# 28-MIPI_60_PIN_CONNECTOR.net
KiCad netlist of a schematic drawn in Altium Designer
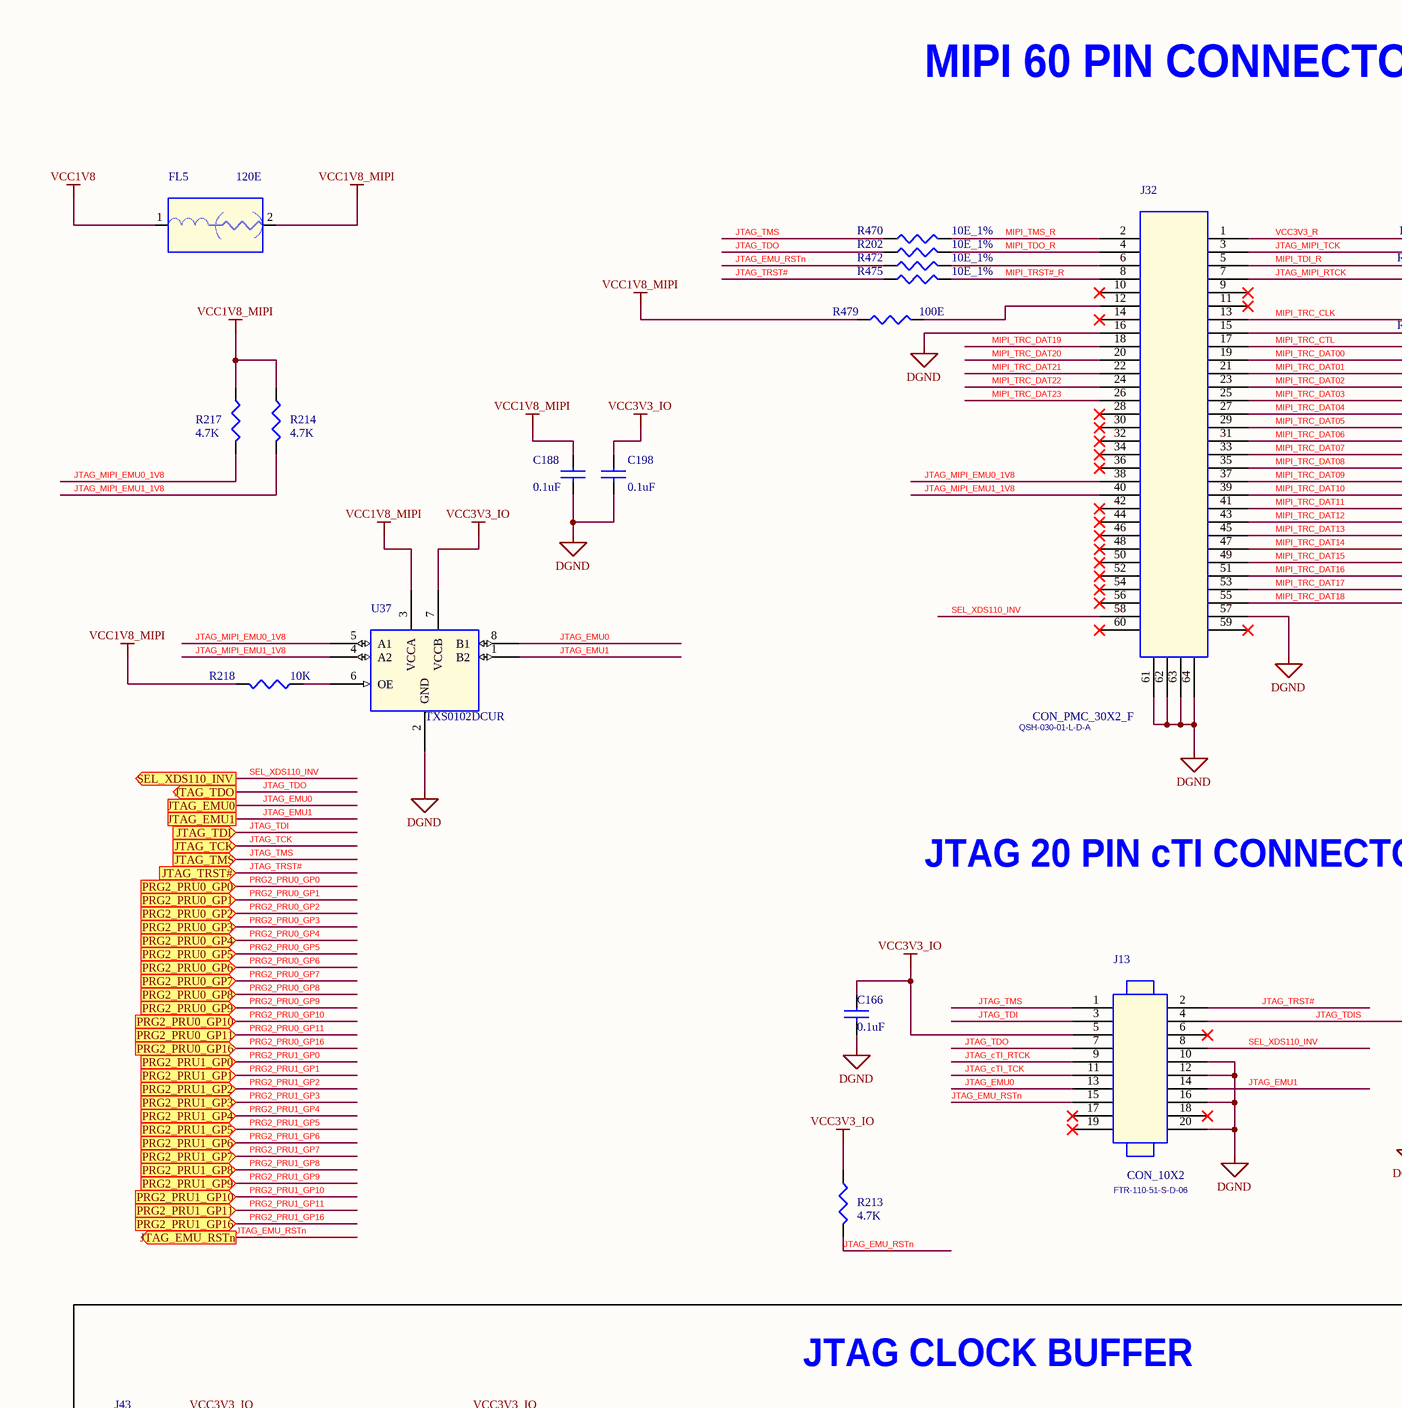
[diagram p0: 28-MIPI 60 PIN CONNECTOR.SchDoc, top left]
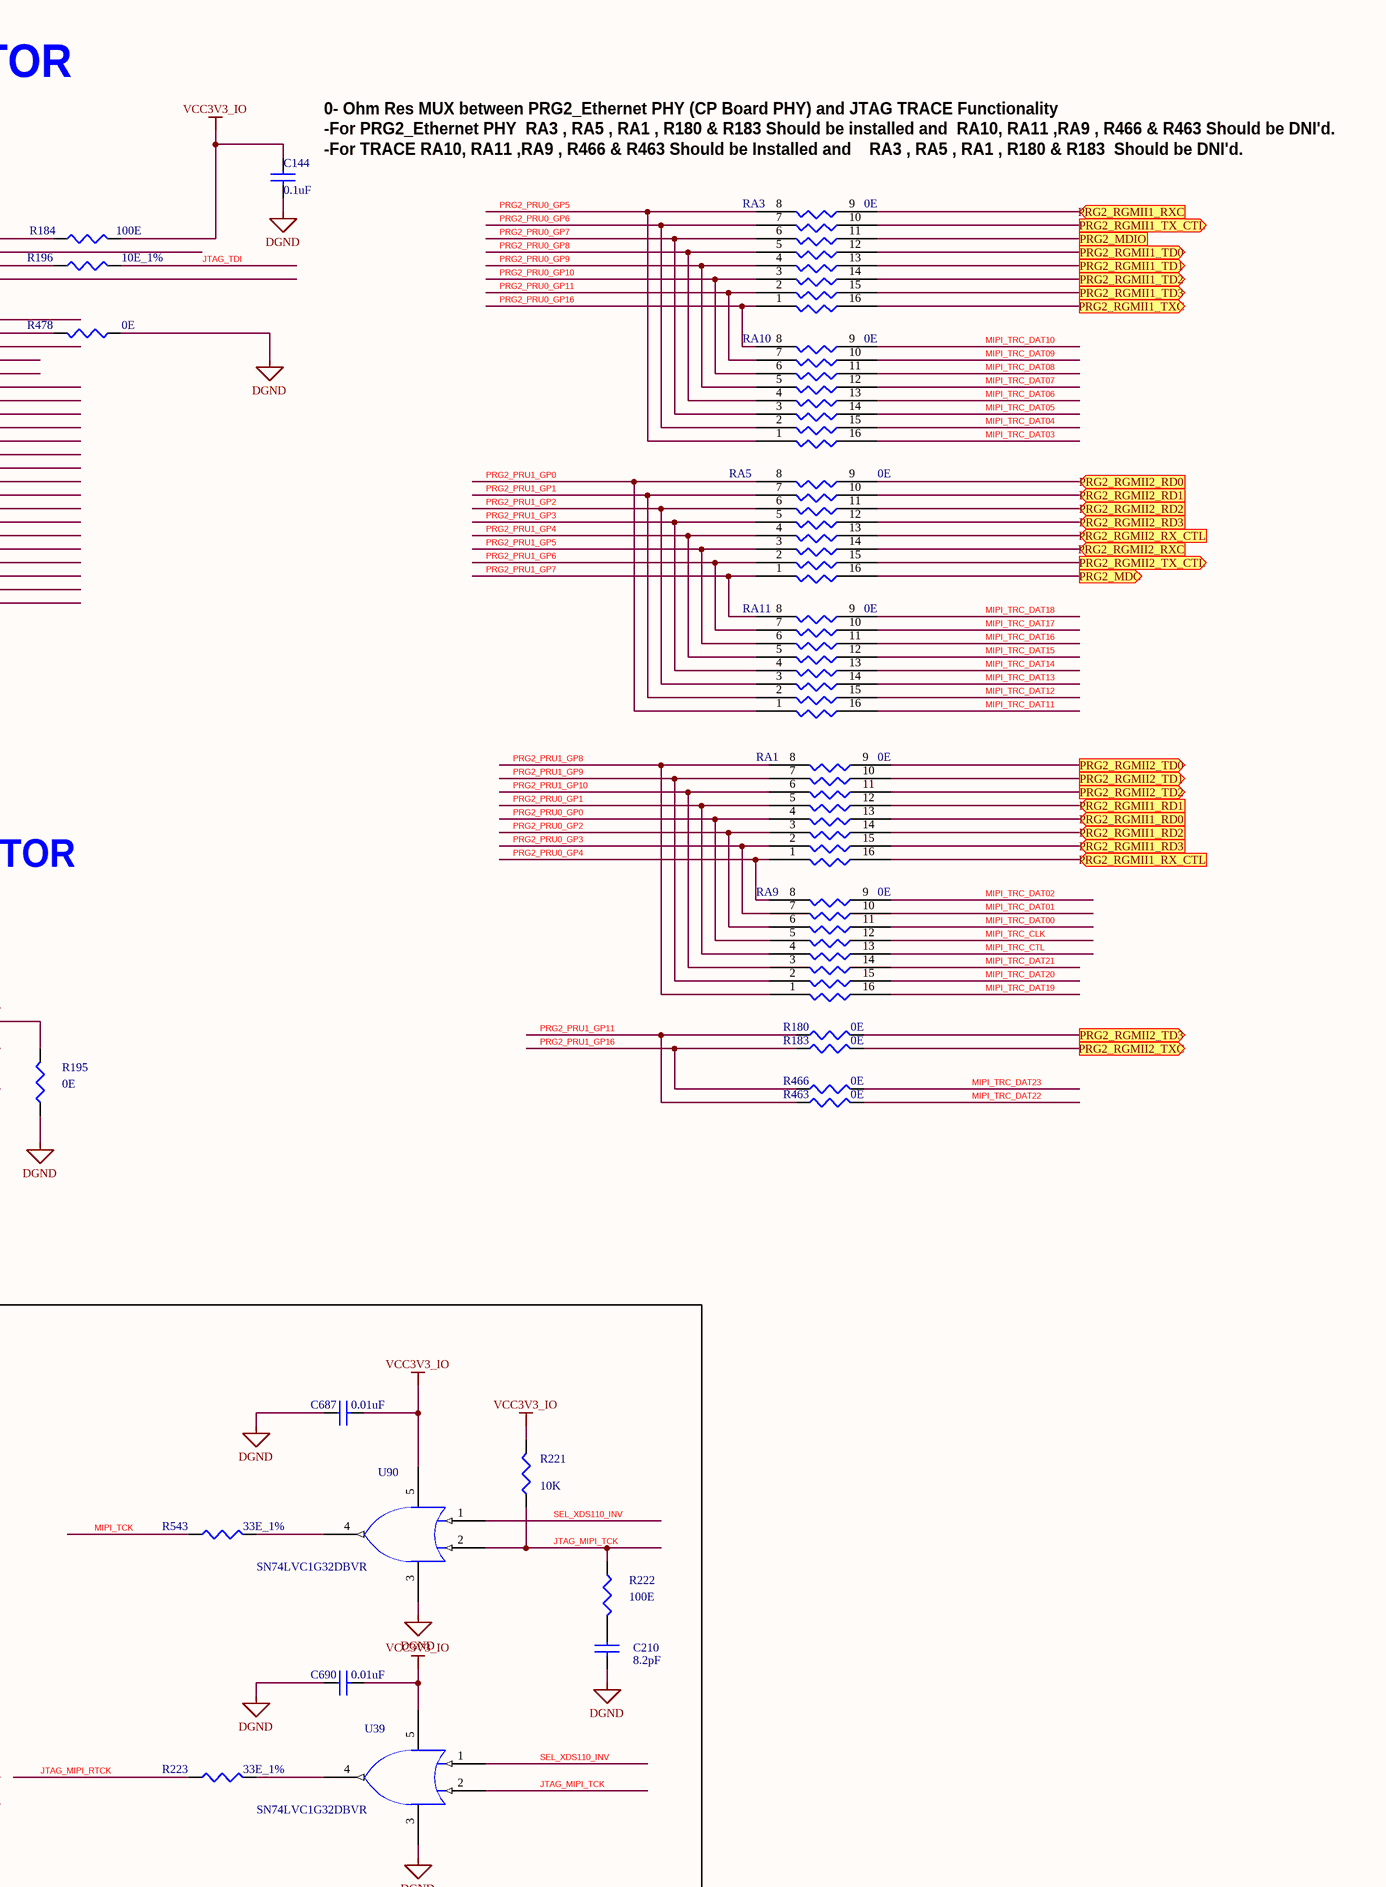
[diagram p1: 28-MIPI 60 PIN CONNECTOR.SchDoc, top right]
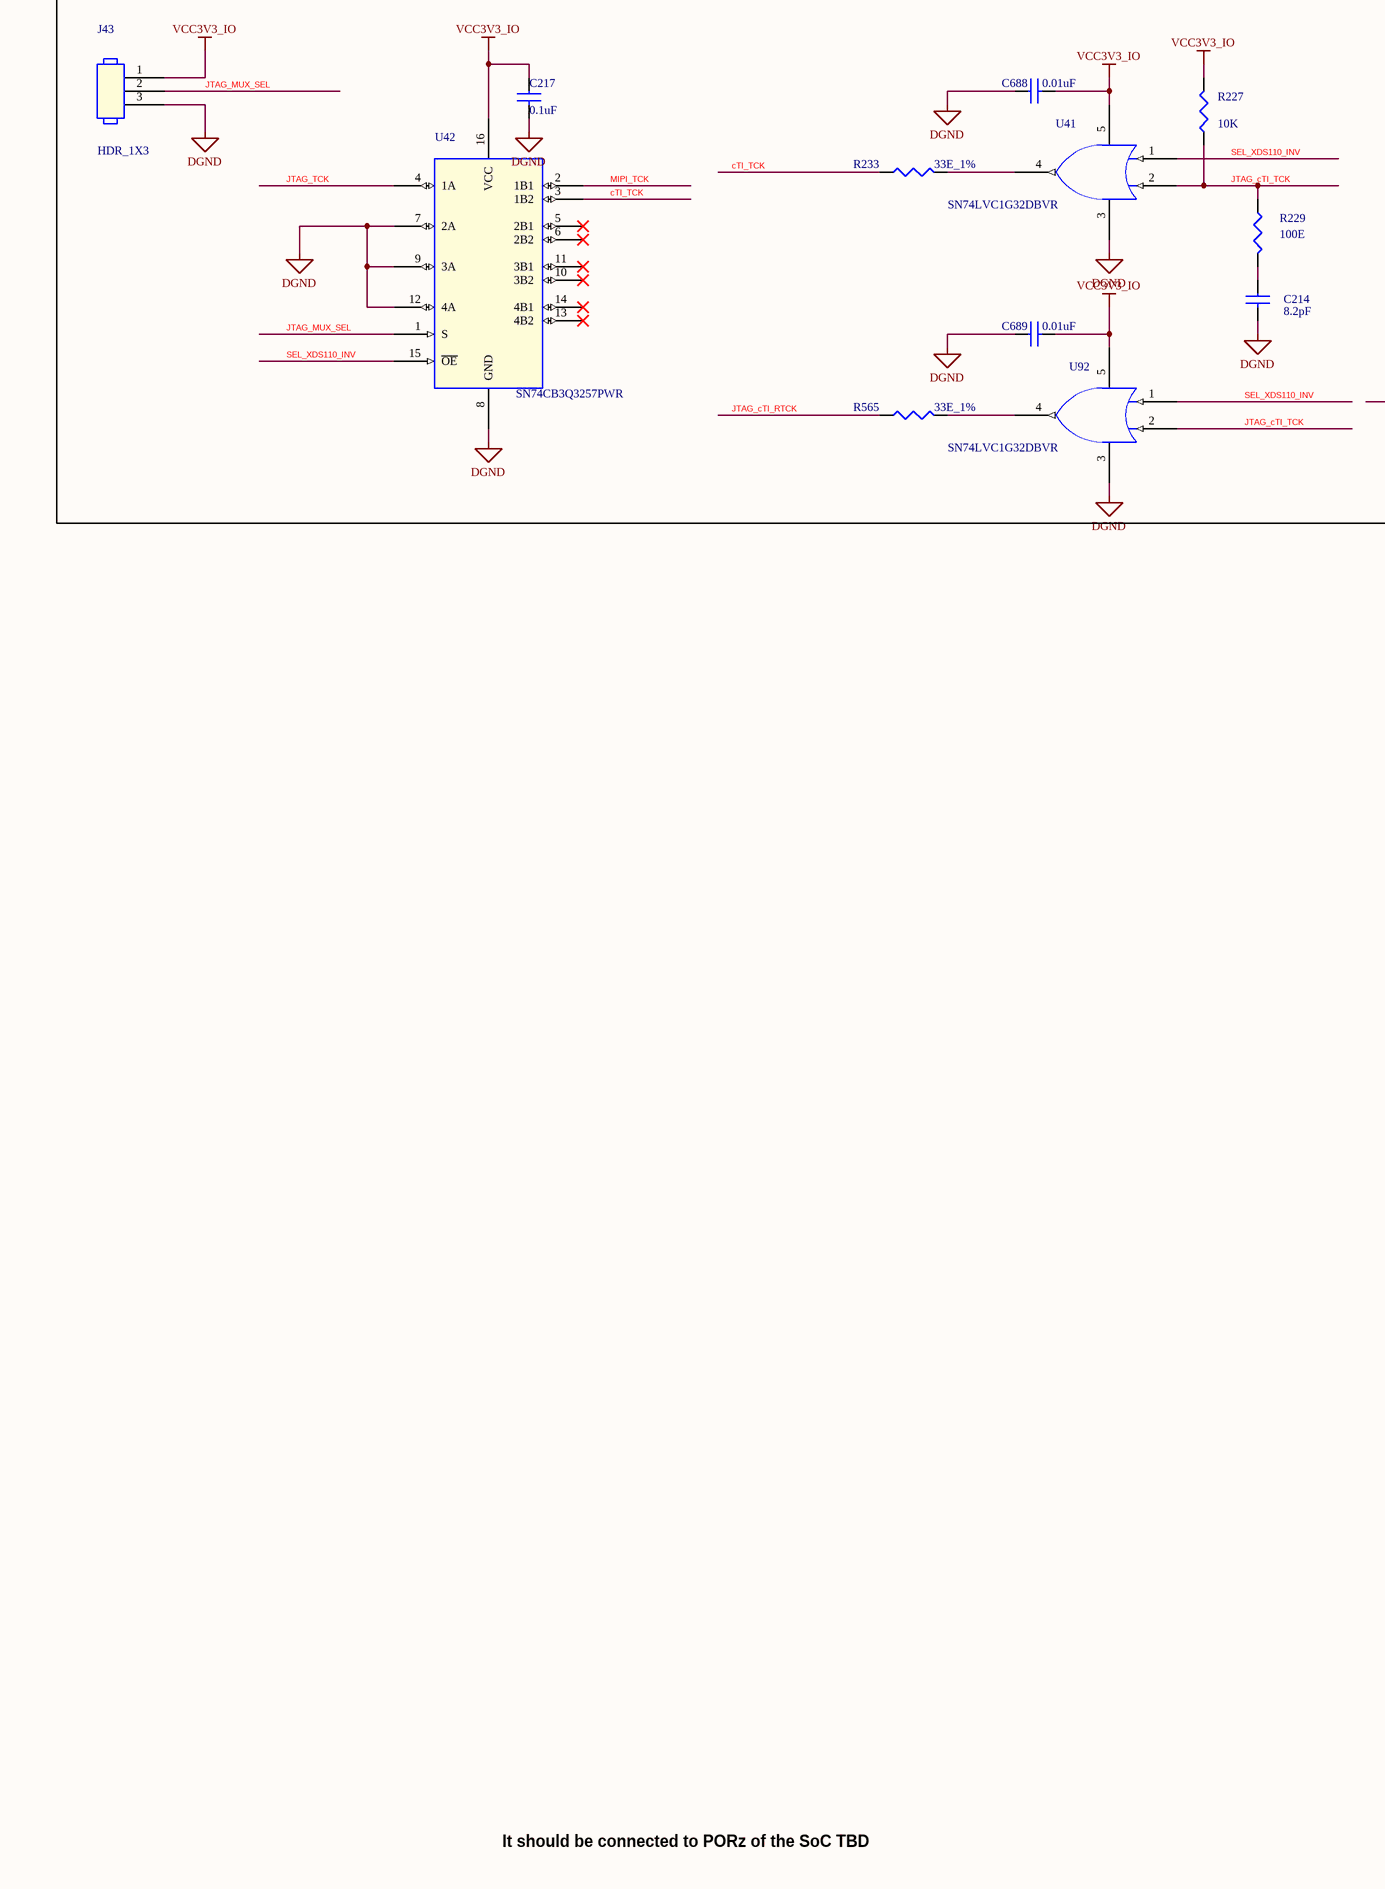
[diagram p2: 28-MIPI 60 PIN CONNECTOR.SchDoc, bottom left]
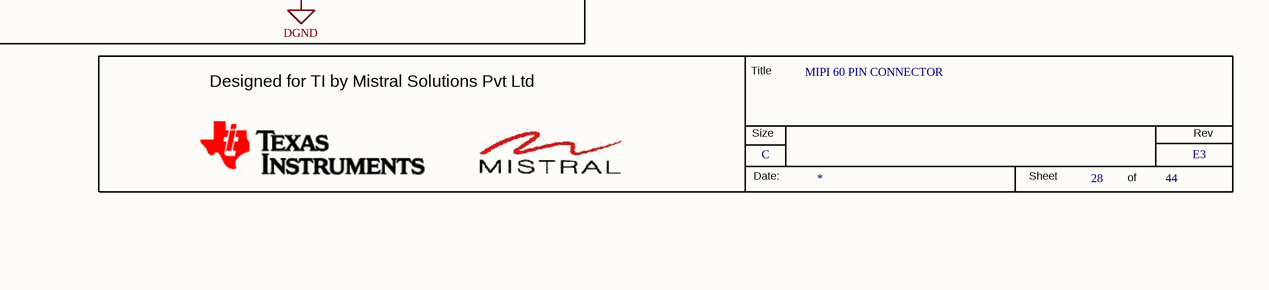
[diagram p3: 28-MIPI 60 PIN CONNECTOR.SchDoc, bottom right]

(export (version "E")
  (design (tool "Eeschema 10.0.6"))
  (components
    (comp (ref "C144")
      (value "0.1uF")
      (footprint "CAP0201_0-5")
      (description "CAP CERAMIC 0.1uF 16V 10% X5R 0201")
      (fields
        (field (name "MISTRAL PART NO") "120009030072-R")
        (field (name "MFR_PART_NUMBER") "GRM033R61C104KE84J")
      )
      (libsource (lib "*") (part "CAP_Dup5"))
    )
    (comp (ref "C166")
      (value "0.1uF")
      (footprint "CAP0201_0-5")
      (description "CAP CERAMIC 0.1uF 16V 10% X5R 0201")
      (fields
        (field (name "MISTRAL PART NO") "120009030072-R")
        (field (name "MFR_PART_NUMBER") "GRM033R61C104KE84J")
      )
      (libsource (lib "*") (part "CAP_Dup5"))
    )
    (comp (ref "C188")
      (value "0.1uF")
      (footprint "CAP0201_0-5")
      (description "CAP CERAMIC 0.1uF 16V 10% X5R 0201")
      (fields (field (name "DISTRIBUTOR_PART_NUMBER") "490-16742-1-ND") (field (name "VOLTAGE") "16V"))
      (libsource (lib "*") (part "CAP_Dup5"))
    )
    (comp (ref "C198")
      (value "0.1uF")
      (footprint "CAP0201_0-5")
      (description "CAP CERAMIC 0.1uF 16V 10% X5R 0201")
      (fields
        (field (name "MISTRAL PART NO") "120009030072-R")
        (field (name "MFR_PART_NUMBER") "GRM033R61C104KE84J")
      )
      (libsource (lib "*") (part "CAP_Dup5"))
    )
    (comp (ref "C210")
      (value "8.2pF")
      (footprint "CAP0402_0-75")
      (description "CAP CERAMIC 8.2pF 50V 0.5pF C0G(NP0) 0402")
      (fields (field (name "DISTRIBUTOR_PART_NUMBER") "GCM1555C1H8R2DA16D-ND") (field (name "VOLTAGE") "50V"))
      (libsource (lib "*") (part "CAP_Dup5"))
    )
    (comp (ref "C214")
      (value "8.2pF")
      (footprint "CAP0402_0-75")
      (description "CAP CERAMIC 8.2pF 50V 0.5pF C0G(NP0) 0402")
      (fields (field (name "DISTRIBUTOR_PART_NUMBER") "GCM1555C1H8R2DA16D-ND") (field (name "VOLTAGE") "50V"))
      (libsource (lib "*") (part "CAP_Dup5"))
    )
    (comp (ref "C217")
      (value "0.1uF")
      (footprint "CAP0201_0-5")
      (description "CAP CERAMIC 0.1uF 16V 10% X5R 0201")
      (fields (field (name "DISTRIBUTOR_PART_NUMBER") "490-16742-1-ND") (field (name "VOLTAGE") "16V"))
      (libsource (lib "*") (part "CAP_Dup4"))
    )
    (comp (ref "C687")
      (value "0.01uF")
      (footprint "CAP0201_0-5")
      (description "CAP CERAMIC 0.01uF 25V 10% X5R 0201")
      (fields (field (name "DISTRIBUTOR_PART_NUMBER") "GRM033R61E103KA12J-ND") (field (name "VOLTAGE") "25V"))
      (libsource (lib "*") (part "CAP_Dup5"))
    )
    (comp (ref "C688")
      (value "0.01uF")
      (footprint "CAP0201_0-5")
      (description "CAP CERAMIC 0.01uF 25V 10% X5R 0201")
      (fields (field (name "DISTRIBUTOR_PART_NUMBER") "GRM033R61E103KA12J-ND") (field (name "VOLTAGE") "25V"))
      (libsource (lib "*") (part "CAP_Dup5"))
    )
    (comp (ref "C689")
      (value "0.01uF")
      (footprint "CAP0201_0-5")
      (description "CAP CERAMIC 0.01uF 25V 10% X5R 0201")
      (fields (field (name "DISTRIBUTOR_PART_NUMBER") "GRM033R61E103KA12J-ND") (field (name "VOLTAGE") "25V"))
      (libsource (lib "*") (part "CAP_Dup5"))
    )
    (comp (ref "C690")
      (value "0.01uF")
      (footprint "CAP0201_0-5")
      (description "CAP CERAMIC 0.01uF 25V 10% X5R 0201")
      (fields (field (name "DISTRIBUTOR_PART_NUMBER") "GRM033R61E103KA12J-ND") (field (name "VOLTAGE") "25V"))
      (libsource (lib "*") (part "CAP_Dup5"))
    )
    (comp (ref "FL5")
      (value "120E")
      (footprint "EMIFIL_BLM15A_0402_0-6")
      (description "FERRITE CHIP 120E 1.3A 0402")
      (fields (field (name "DISTRIBUTOR_PART_NUMBER") "490-5203-1-ND") (field (name "VOLTAGE") "NA"))
      (libsource (lib "*") (part "EMIFILTER_IND"))
    )
    (comp (ref "J13")
      (value "CON_10X2")
      (footprint "CON_10X2_FTR-110-51-S-D_P_S_S")
      (description "CON 10X2 1.27MM PITCH MALE SMD")
      (fields
        (field (name "DISTRIBUTOR_PART_NUMBER") "FTR-110-51-S-D-06-ND")
        (field (name "VOLTAGE") "NA")
        (field (name "MFR_PART_NUMBER") "FTR-110-51-S-D-06")
      )
      (libsource (lib "*") (part "CON_10X2"))
    )
    (comp (ref "J32")
      (value "CON_PMC_30X2_F")
      (footprint "CON_PMC30X2_QSH-030-01-L_S_S_S")
      (description "CON PMC 30X2 0.50MM PITCH FEMALE ST SMD")
      (fields
        (field (name "MISTRAL PART NO") "150009030606")
        (field (name "MFR_PART_NUMBER") "QSH-030-01-L-D-A")
      )
      (libsource (lib "*") (part "CON_PMC_30X2_F"))
    )
    (comp (ref "J43")
      (value "HDR_1X3")
      (footprint "HDR_3X1_100_S_T")
      (description "HDR 1X3 2.54MM PITCH ST TH")
      (fields (field (name "DISTRIBUTOR_PART_NUMBER") "609-3471-ND") (field (name "VOLTAGE") "NA"))
      (libsource (lib "*") (part "HEADER_3X1"))
    )
    (comp (ref "R180")
      (value "0E")
      (footprint "RES0402_0-5")
      (description "RES 0E 1/16W 0402")
      (fields (field (name "DISTRIBUTOR_PART_NUMBER") "541-0.0JCT-ND") (field (name "VOLTAGE") "NA"))
      (libsource (lib "*") (part "RESISTOR_Dup4"))
    )
    (comp (ref "R183")
      (value "0E")
      (footprint "RES0402_0-5")
      (description "RES 0E 1/16W 0402")
      (fields
        (field (name "MISTRAL PART NO") "110010080019-P")
        (field (name "MFR_PART_NUMBER") "CRCW04020000Z0ED")
      )
      (libsource (lib "*") (part "RESISTOR_Dup4"))
    )
    (comp (ref "R184")
      (value "100E")
      (footprint "RES0402_0-5")
      (description "RES 100E 1/16W 5% 0402")
      (fields (field (name "DISTRIBUTOR_PART_NUMBER") "541-100JCT-ND") (field (name "VOLTAGE") "NA"))
      (libsource (lib "*") (part "RESISTOR_Dup1"))
    )
    (comp (ref "R195")
      (value "0E")
      (footprint "RES0402_0-5")
      (description "RES 0E 1/16W 0402")
      (fields (field (name "DISTRIBUTOR_PART_NUMBER") "541-0.0JCT-ND") (field (name "VOLTAGE") "NA"))
      (libsource (lib "*") (part "RESISTOR_Dup4"))
    )
    (comp (ref "R196")
      (value "10E_1%")
      (footprint "TMDX654GPEVM_BRD:RES0402_0-5")
      (description "RES 10E 1/16W 1% 0402")
      (fields (field (name "VOLTAGE") "NA") (field (name "MISTRAL PART NO") "110018020004-R"))
      (libsource (lib "*") (part "RESISTOR_Dup2"))
    )
    (comp (ref "R202")
      (value "10E_1%")
      (footprint "TMDX654GPEVM_BRD:RES0402_0-5")
      (description "RES 10E 1/16W 1% 0402")
      (fields (field (name "VOLTAGE") "NA") (field (name "DISTRIBUTOR_PART_NUMBER") "311-10.0LRCT-ND"))
      (libsource (lib "*") (part "RESISTOR_Dup2"))
    )
    (comp (ref "R213")
      (value "4.7K")
      (footprint "RES0402")
      (description "RES 4.7K 1/16W 5% 0402")
      (fields
        (field (name "MISTRAL PART NO") "110009030792-R")
        (field (name "MFR_PART_NUMBER") "RC0402JR-074K7L")
      )
      (libsource (lib "*") (part "RESISTOR_Dup3"))
    )
    (comp (ref "R214")
      (value "4.7K")
      (footprint "RES0402")
      (description "RES 4.7K 1/16W 5% 0402")
      (fields (field (name "DISTRIBUTOR_PART_NUMBER") "311-4.7KJRCT-ND") (field (name "VOLTAGE") "NA"))
      (libsource (lib "*") (part "RESISTOR_Dup3"))
    )
    (comp (ref "R217")
      (value "4.7K")
      (footprint "RES0402")
      (description "RES 4.7K 1/16W 5% 0402")
      (fields
        (field (name "MISTRAL PART NO") "110009030792-R")
        (field (name "MFR_PART_NUMBER") "RC0402JR-074K7L")
      )
      (libsource (lib "*") (part "RESISTOR_Dup3"))
    )
    (comp (ref "R218")
      (value "10K")
      (footprint "RES0402_0-5")
      (description "RES 10K 1/16W 5% 0402")
      (fields (field (name "DISTRIBUTOR_PART_NUMBER") "311-10KJRCT-ND") (field (name "VOLTAGE") "NA"))
      (libsource (lib "*") (part "RESISTOR_Dup5"))
    )
    (comp (ref "R221")
      (value "10K")
      (footprint "RES0402_0-5")
      (description "RES 10K 1/16W 5% 0402")
      (fields
        (field (name "MISTRAL PART NO") "110009030208-R")
        (field (name "MFR_PART_NUMBER") "RC0402JR-0710KL")
      )
      (libsource (lib "*") (part "RESISTOR_Dup5"))
    )
    (comp (ref "R222")
      (value "100E")
      (footprint "RES0402_0-5")
      (description "RES 100E 1/16W 5% 0402")
      (fields
        (field (name "MISTRAL PART NO") "110009030164-R")
        (field (name "MFR_PART_NUMBER") "CRCW0402100RJNED")
      )
      (libsource (lib "*") (part "RESISTOR_Dup5"))
    )
    (comp (ref "R223")
      (value "33E_1%")
      (footprint "RES0402_0-5")
      (description "RES 33E 1/16W 1% 0402")
      (fields
        (field (name "MISTRAL PART NO") "110014110006-R")
        (field (name "MFR_PART_NUMBER") "ERJ-2RKF33R0X")
      )
      (libsource (lib "*") (part "RESISTOR_Dup5"))
    )
    (comp (ref "R227")
      (value "10K")
      (footprint "RES0402_0-5")
      (description "RES 10K 1/16W 5% 0402")
      (fields
        (field (name "MISTRAL PART NO") "110009030208-R")
        (field (name "MFR_PART_NUMBER") "RC0402JR-0710KL")
      )
      (libsource (lib "*") (part "RESISTOR_Dup5"))
    )
    (comp (ref "R229")
      (value "100E")
      (footprint "RES0402_0-5")
      (description "RES 100E 1/16W 5% 0402")
      (fields (field (name "DISTRIBUTOR_PART_NUMBER") "541-100JCT-ND") (field (name "VOLTAGE") "NA"))
      (libsource (lib "*") (part "RESISTOR_Dup5"))
    )
    (comp (ref "R233")
      (value "33E_1%")
      (footprint "RES0402_0-5")
      (description "RES 33E 1/16W 1% 0402")
      (fields
        (field (name "MISTRAL PART NO") "110014110006-R")
        (field (name "MFR_PART_NUMBER") "ERJ-2RKF33R0X")
      )
      (libsource (lib "*") (part "RESISTOR_Dup5"))
    )
    (comp (ref "R463")
      (value "0E")
      (footprint "RES0402_0-5")
      (description "RES 0E 1/16W 0402")
      (fields (field (name "DISTRIBUTOR_PART_NUMBER") "541-0.0JCT-ND") (field (name "VOLTAGE") "NA"))
      (libsource (lib "*") (part "RESISTOR_Dup4"))
    )
    (comp (ref "R466")
      (value "0E")
      (footprint "RES0402_0-5")
      (description "RES 0E 1/16W 0402")
      (fields (field (name "DISTRIBUTOR_PART_NUMBER") "541-0.0JCT-ND") (field (name "VOLTAGE") "NA"))
      (libsource (lib "*") (part "RESISTOR_Dup4"))
    )
    (comp (ref "R470")
      (value "10E_1%")
      (footprint "TMDX654GPEVM_BRD:RES0402_0-5")
      (description "RES 10E 1/16W 1% 0402")
      (fields (field (name "VOLTAGE") "NA") (field (name "MISTRAL PART NO") "110018020004-R"))
      (libsource (lib "*") (part "RESISTOR_Dup2"))
    )
    (comp (ref "R472")
      (value "10E_1%")
      (footprint "TMDX654GPEVM_BRD:RES0402_0-5")
      (description "RES 10E 1/16W 1% 0402")
      (fields (field (name "VOLTAGE") "NA") (field (name "MISTRAL PART NO") "110018020004-R"))
      (libsource (lib "*") (part "RESISTOR_Dup2"))
    )
    (comp (ref "R475")
      (value "10E_1%")
      (footprint "TMDX654GPEVM_BRD:RES0402_0-5")
      (description "RES 10E 1/16W 1% 0402")
      (fields (field (name "VOLTAGE") "NA") (field (name "DISTRIBUTOR_PART_NUMBER") "311-10.0LRCT-ND"))
      (libsource (lib "*") (part "RESISTOR_Dup2"))
    )
    (comp (ref "R478")
      (value "0E")
      (footprint "TMDX654GPEVM_BRD:RES0402_0-5")
      (description "RES 0E 1/16W 0402")
      (fields (field (name "VOLTAGE") "NA") (field (name "MISTRAL PART NO") "110010080019-P"))
      (libsource (lib "*") (part "RESISTOR_Dup2"))
    )
    (comp (ref "R479")
      (value "100E")
      (footprint "RES0402_0-5")
      (description "RES 100E 1/16W 5% 0402")
      (fields (field (name "DISTRIBUTOR_PART_NUMBER") "541-100JCT-ND") (field (name "VOLTAGE") "NA"))
      (libsource (lib "*") (part "RESISTOR_Dup1"))
    )
    (comp (ref "R543")
      (value "33E_1%")
      (footprint "RES0402_0-5")
      (description "RES 33E 1/16W 1% 0402")
      (fields
        (field (name "MISTRAL PART NO") "110014110006-R")
        (field (name "MFR_PART_NUMBER") "ERJ-2RKF33R0X")
      )
      (libsource (lib "*") (part "RESISTOR_Dup5"))
    )
    (comp (ref "R565")
      (value "33E_1%")
      (footprint "RES0402_0-5")
      (description "RES 33E 1/16W 1% 0402")
      (fields (field (name "DISTRIBUTOR_PART_NUMBER") "P33.0LCT-ND") (field (name "VOLTAGE") "NA"))
      (libsource (lib "*") (part "RESISTOR_Dup5"))
    )
    (comp (ref "RA1")
      (value "0E")
      (footprint "RESA_0402-8")
      (description "RES ARRAY 8 0E 0402")
      (fields
        (field (name "DISTRIBUTOR_PART_NUMBER") "Y1000CT-ND")
        (field (name "MFR_PART_NUMBER") "EXB-2HVR000V")
      )
      (libsource (lib "*") (part "RESARR_ISO8_0402"))
    )
    (comp (ref "RA3")
      (value "0E")
      (footprint "RESA_0402-8")
      (description "RES ARRAY 8 0E 0402")
      (fields
        (field (name "DISTRIBUTOR_PART_NUMBER") "Y1000CT-ND")
        (field (name "MFR_PART_NUMBER") "EXB-2HVR000V")
      )
      (libsource (lib "*") (part "RESARR_ISO8_0402"))
    )
    (comp (ref "RA5")
      (value "0E")
      (footprint "RESA_0402-8")
      (description "RES ARRAY 8 0E 0402")
      (fields
        (field (name "DISTRIBUTOR_PART_NUMBER") "Y1000CT-ND")
        (field (name "MFR_PART_NUMBER") "EXB-2HVR000V")
      )
      (libsource (lib "*") (part "RESARR_ISO8_0402"))
    )
    (comp (ref "RA9")
      (value "0E")
      (footprint "RESA_0402-8")
      (description "RES ARRAY 8 0E 0402")
      (fields
        (field (name "MISTRAL PART NO") "110009030004-R")
        (field (name "MFR_PART_NUMBER") "EXB-2HVR000V")
      )
      (libsource (lib "*") (part "RESARR_ISO8_0402"))
    )
    (comp (ref "RA10")
      (value "0E")
      (footprint "RESA_0402-8")
      (description "RES ARRAY 8 0E 0402")
      (fields
        (field (name "MISTRAL PART NO") "110009030004-R")
        (field (name "MFR_PART_NUMBER") "EXB-2HVR000V")
      )
      (libsource (lib "*") (part "RESARR_ISO8_0402"))
    )
    (comp (ref "RA11")
      (value "0E")
      (footprint "RESA_0402-8")
      (description "RES ARRAY 8 0E 0402")
      (fields
        (field (name "MISTRAL PART NO") "110009030004-R")
        (field (name "MFR_PART_NUMBER") "EXB-2HVR000V")
      )
      (libsource (lib "*") (part "RESARR_ISO8_0402"))
    )
    (comp (ref "U37")
      (value "TXS0102DCUR")
      (footprint "VSSOP8_19-68_85X95_0-9")
      (description "IC 2BIT BI-DIR VOLTAGE-LEVEL TRANSLATOR US8(VSSOP8)")
      (fields
        (field (name "MISTRAL PART NO") "141009030376-R")
        (field (name "TOLERANCE") "NA")
        (field (name "LIBRARY PATH") "Y~{:}MIS_DATABAS~{E}Librar~{y}ALTIUM_TOO~{L}SCHEMATICS_PART~{S}MS_MISCINTERFACE_Library.schlib")
      )
      (libsource (lib "*") (part "TXS0102DCUR_VSSOP8"))
    )
    (comp (ref "U39")
      (value "SN74LVC1G32DBVR")
      (footprint "SOT23-5_1-5")
      (description "IC SINGAL 2 INPUT POSITIVE OR GATE SOT23-5")
      (fields (field (name "MISTRAL PART NO") "141009030236-R") (field (name "TOLERANCE") "NA"))
      (libsource (lib "*") (part "SN74LVC1G32DBVR_SOT23-5"))
    )
    (comp (ref "U41")
      (value "SN74LVC1G32DBVR")
      (footprint "SOT23-5_1-5")
      (description "IC SINGAL 2 INPUT POSITIVE OR GATE SOT23-5")
      (fields (field (name "DISTRIBUTOR_PART_NUMBER") "296-9847-1-ND") (field (name "VOLTAGE") "NA"))
      (libsource (lib "*") (part "SN74LVC1G32DBVR_SOT23-5"))
    )
    (comp (ref "U42")
      (value "SN74CB3Q3257PWR")
      (footprint "TSSOP16_25-59_205X180")
      (description "IC 4BIT 1-OF-2 FET MULTIPLEXER/DEMULTIPLEXER TSSOP16")
      (fields
        (field (name "MISTRAL PART NO") "141009030117-R")
        (field (name "DISTRIBUTOR_PART_NUMBER") "296-19138-1-ND")
      )
      (libsource (lib "*") (part "SN74CB3Q3257PWR_TSSOP16"))
    )
    (comp (ref "U90")
      (value "SN74LVC1G32DBVR")
      (footprint "SOT23-5_1-5")
      (description "IC SINGAL 2 INPUT POSITIVE OR GATE SOT23-5")
      (fields (field (name "MISTRAL PART NO") "141009030236-R") (field (name "TOLERANCE") "NA"))
      (libsource (lib "*") (part "SN74LVC1G32DBVR_SOT23-5"))
    )
    (comp (ref "U92")
      (value "SN74LVC1G32DBVR")
      (footprint "SOT23-5_1-5")
      (description "IC SINGAL 2 INPUT POSITIVE OR GATE SOT23-5")
      (fields (field (name "DISTRIBUTOR_PART_NUMBER") "296-9847-1-ND") (field (name "VOLTAGE") "NA"))
      (libsource (lib "*") (part "SN74LVC1G32DBVR_SOT23-5"))
    )
  )
  (nets
    (net (code "1") (name "/JTAG_EMU0") (class "Default")
      (node (ref "J13") (pin "13") (pinfunction "13_13") (pintype "passive"))
      (node (ref "U37") (pin "8") (pinfunction "B1_8") (pintype "bidirectional"))
    )
    (net (code "2") (name "/JTAG_EMU1") (class "Default")
      (node (ref "J13") (pin "14") (pinfunction "14_14") (pintype "passive"))
      (node (ref "U37") (pin "1") (pinfunction "B2_1") (pintype "bidirectional"))
    )
    (net (code "3") (name "/JTAG_EMU_RSTn") (class "Default")
      (node (ref "J13") (pin "15") (pinfunction "15_15") (pintype "passive"))
      (node (ref "R213") (pin "2") (pinfunction "2_2") (pintype "passive"))
      (node (ref "R472") (pin "1") (pinfunction "1_1") (pintype "passive"))
    )
    (net (code "4") (name "/JTAG_MIPI_EMU0_1V8") (class "Default")
      (node (ref "J32") (pin "38") (pinfunction "38_38") (pintype "passive"))
      (node (ref "R217") (pin "2") (pinfunction "2_2") (pintype "passive"))
      (node (ref "U37") (pin "5") (pinfunction "A1_5") (pintype "bidirectional"))
    )
    (net (code "5") (name "/JTAG_MIPI_EMU1_1V8") (class "Default")
      (node (ref "J32") (pin "40") (pinfunction "40_40") (pintype "passive"))
      (node (ref "R214") (pin "2") (pinfunction "2_2") (pintype "passive"))
      (node (ref "U37") (pin "4") (pinfunction "A2_4") (pintype "bidirectional"))
    )
    (net (code "6") (name "/JTAG_MIPI_RTCK") (class "Default")
      (node (ref "J32") (pin "7") (pinfunction "7_7") (pintype "passive"))
      (node (ref "R223") (pin "1") (pinfunction "1_1") (pintype "passive"))
    )
    (net (code "7") (name "/JTAG_MIPI_TCK") (class "Default")
      (node (ref "J32") (pin "3") (pinfunction "3_3") (pintype "passive"))
      (node (ref "R221") (pin "1") (pinfunction "1_1") (pintype "passive"))
      (node (ref "R222") (pin "1") (pinfunction "1_1") (pintype "passive"))
      (node (ref "U39") (pin "2") (pinfunction "B_2") (pintype "input"))
      (node (ref "U90") (pin "2") (pinfunction "B_2") (pintype "input"))
    )
    (net (code "8") (name "/JTAG_MUX_SEL") (class "Default")
      (node (ref "J43") (pin "2") (pinfunction "2_2") (pintype "passive"))
      (node (ref "U42") (pin "1") (pinfunction "S_1") (pintype "input"))
    )
    (net (code "9") (name "/JTAG_TCK") (class "Default")
      (node (ref "U42") (pin "4") (pinfunction "1A_4") (pintype "bidirectional"))
    )
    (net (code "10") (name "/JTAG_TDI") (class "Default")
      (node (ref "J13") (pin "3") (pinfunction "3_3") (pintype "passive"))
      (node (ref "R196") (pin "2") (pinfunction "2_2") (pintype "passive"))
    )
    (net (code "11") (name "/JTAG_TDIS") (class "Default")
      (node (ref "J13") (pin "4") (pinfunction "4_4") (pintype "passive"))
      (node (ref "R195") (pin "2") (pinfunction "2_2") (pintype "passive"))
    )
    (net (code "12") (name "/JTAG_TDO") (class "Default")
      (node (ref "J13") (pin "7") (pinfunction "7_7") (pintype "passive"))
      (node (ref "R202") (pin "1") (pinfunction "1_1") (pintype "passive"))
    )
    (net (code "13") (name "/JTAG_TMS") (class "Default")
      (node (ref "J13") (pin "1") (pinfunction "1_1") (pintype "passive"))
      (node (ref "R470") (pin "1") (pinfunction "1_1") (pintype "passive"))
    )
    (net (code "14") (name "/JTAG_TRST#") (class "Default")
      (node (ref "J13") (pin "2") (pinfunction "2_2") (pintype "passive"))
      (node (ref "R475") (pin "1") (pinfunction "1_1") (pintype "passive"))
    )
    (net (code "15") (name "/JTAG_cTI_RTCK") (class "Default")
      (node (ref "J13") (pin "9") (pinfunction "9_9") (pintype "passive"))
      (node (ref "R565") (pin "1") (pinfunction "1_1") (pintype "passive"))
    )
    (net (code "16") (name "/JTAG_cTI_TCK") (class "Default")
      (node (ref "J13") (pin "11") (pinfunction "11_11") (pintype "passive"))
      (node (ref "R227") (pin "1") (pinfunction "1_1") (pintype "passive"))
      (node (ref "R229") (pin "1") (pinfunction "1_1") (pintype "passive"))
      (node (ref "U41") (pin "2") (pinfunction "B_2") (pintype "input"))
      (node (ref "U92") (pin "2") (pinfunction "B_2") (pintype "input"))
    )
    (net (code "17") (name "/MIPI_TCK") (class "Default")
      (node (ref "R543") (pin "1") (pinfunction "1_1") (pintype "passive"))
      (node (ref "U42") (pin "2") (pinfunction "1B1_2") (pintype "bidirectional"))
    )
    (net (code "18") (name "/MIPI_TDI_R") (class "Default")
      (node (ref "J32") (pin "5") (pinfunction "5_5") (pintype "passive"))
      (node (ref "R196") (pin "1") (pinfunction "1_1") (pintype "passive"))
    )
    (net (code "19") (name "/MIPI_TDO_R") (class "Default")
      (node (ref "J32") (pin "4") (pinfunction "4_4") (pintype "passive"))
      (node (ref "R202") (pin "2") (pinfunction "2_2") (pintype "passive"))
    )
    (net (code "20") (name "/MIPI_TMS_R") (class "Default")
      (node (ref "J32") (pin "2") (pinfunction "2_2") (pintype "passive"))
      (node (ref "R470") (pin "2") (pinfunction "2_2") (pintype "passive"))
    )
    (net (code "21") (name "/MIPI_TRC_CLK") (class "Default")
      (node (ref "J32") (pin "13") (pinfunction "13_13") (pintype "passive"))
      (node (ref "RA9") (pin "12") (pinfunction "12_12") (pintype "passive"))
    )
    (net (code "22") (name "/MIPI_TRC_CTL") (class "Default")
      (node (ref "J32") (pin "17") (pinfunction "17_17") (pintype "passive"))
      (node (ref "RA9") (pin "13") (pinfunction "13_13") (pintype "passive"))
    )
    (net (code "23") (name "/MIPI_TRC_DAT00") (class "Default")
      (node (ref "J32") (pin "19") (pinfunction "19_19") (pintype "passive"))
      (node (ref "RA9") (pin "11") (pinfunction "11_11") (pintype "passive"))
    )
    (net (code "24") (name "/MIPI_TRC_DAT01") (class "Default")
      (node (ref "J32") (pin "21") (pinfunction "21_21") (pintype "passive"))
      (node (ref "RA9") (pin "10") (pinfunction "10_10") (pintype "passive"))
    )
    (net (code "25") (name "/MIPI_TRC_DAT02") (class "Default")
      (node (ref "J32") (pin "23") (pinfunction "23_23") (pintype "passive"))
      (node (ref "RA9") (pin "9") (pinfunction "9_9") (pintype "passive"))
    )
    (net (code "26") (name "/MIPI_TRC_DAT03") (class "Default")
      (node (ref "J32") (pin "25") (pinfunction "25_25") (pintype "passive"))
      (node (ref "RA10") (pin "16") (pinfunction "16_16") (pintype "passive"))
    )
    (net (code "27") (name "/MIPI_TRC_DAT04") (class "Default")
      (node (ref "J32") (pin "27") (pinfunction "27_27") (pintype "passive"))
      (node (ref "RA10") (pin "15") (pinfunction "15_15") (pintype "passive"))
    )
    (net (code "28") (name "/MIPI_TRC_DAT05") (class "Default")
      (node (ref "J32") (pin "29") (pinfunction "29_29") (pintype "passive"))
      (node (ref "RA10") (pin "14") (pinfunction "14_14") (pintype "passive"))
    )
    (net (code "29") (name "/MIPI_TRC_DAT06") (class "Default")
      (node (ref "J32") (pin "31") (pinfunction "31_31") (pintype "passive"))
      (node (ref "RA10") (pin "13") (pinfunction "13_13") (pintype "passive"))
    )
    (net (code "30") (name "/MIPI_TRC_DAT07") (class "Default")
      (node (ref "J32") (pin "33") (pinfunction "33_33") (pintype "passive"))
      (node (ref "RA10") (pin "12") (pinfunction "12_12") (pintype "passive"))
    )
    (net (code "31") (name "/MIPI_TRC_DAT08") (class "Default")
      (node (ref "J32") (pin "35") (pinfunction "35_35") (pintype "passive"))
      (node (ref "RA10") (pin "11") (pinfunction "11_11") (pintype "passive"))
    )
    (net (code "32") (name "/MIPI_TRC_DAT09") (class "Default")
      (node (ref "J32") (pin "37") (pinfunction "37_37") (pintype "passive"))
      (node (ref "RA10") (pin "10") (pinfunction "10_10") (pintype "passive"))
    )
    (net (code "33") (name "/MIPI_TRC_DAT10") (class "Default")
      (node (ref "J32") (pin "39") (pinfunction "39_39") (pintype "passive"))
      (node (ref "RA10") (pin "9") (pinfunction "9_9") (pintype "passive"))
    )
    (net (code "34") (name "/MIPI_TRC_DAT11") (class "Default")
      (node (ref "J32") (pin "41") (pinfunction "41_41") (pintype "passive"))
      (node (ref "RA11") (pin "16") (pinfunction "16_16") (pintype "passive"))
    )
    (net (code "35") (name "/MIPI_TRC_DAT12") (class "Default")
      (node (ref "J32") (pin "43") (pinfunction "43_43") (pintype "passive"))
      (node (ref "RA11") (pin "15") (pinfunction "15_15") (pintype "passive"))
    )
    (net (code "36") (name "/MIPI_TRC_DAT13") (class "Default")
      (node (ref "J32") (pin "45") (pinfunction "45_45") (pintype "passive"))
      (node (ref "RA11") (pin "14") (pinfunction "14_14") (pintype "passive"))
    )
    (net (code "37") (name "/MIPI_TRC_DAT14") (class "Default")
      (node (ref "J32") (pin "47") (pinfunction "47_47") (pintype "passive"))
      (node (ref "RA11") (pin "13") (pinfunction "13_13") (pintype "passive"))
    )
    (net (code "38") (name "/MIPI_TRC_DAT15") (class "Default")
      (node (ref "J32") (pin "49") (pinfunction "49_49") (pintype "passive"))
      (node (ref "RA11") (pin "12") (pinfunction "12_12") (pintype "passive"))
    )
    (net (code "39") (name "/MIPI_TRC_DAT16") (class "Default")
      (node (ref "J32") (pin "51") (pinfunction "51_51") (pintype "passive"))
      (node (ref "RA11") (pin "11") (pinfunction "11_11") (pintype "passive"))
    )
    (net (code "40") (name "/MIPI_TRC_DAT17") (class "Default")
      (node (ref "J32") (pin "53") (pinfunction "53_53") (pintype "passive"))
      (node (ref "RA11") (pin "10") (pinfunction "10_10") (pintype "passive"))
    )
    (net (code "41") (name "/MIPI_TRC_DAT18") (class "Default")
      (node (ref "J32") (pin "55") (pinfunction "55_55") (pintype "passive"))
      (node (ref "RA11") (pin "9") (pinfunction "9_9") (pintype "passive"))
    )
    (net (code "42") (name "/MIPI_TRC_DAT19") (class "Default")
      (node (ref "J32") (pin "18") (pinfunction "18_18") (pintype "passive"))
      (node (ref "RA9") (pin "16") (pinfunction "16_16") (pintype "passive"))
    )
    (net (code "43") (name "/MIPI_TRC_DAT20") (class "Default")
      (node (ref "J32") (pin "20") (pinfunction "20_20") (pintype "passive"))
      (node (ref "RA9") (pin "15") (pinfunction "15_15") (pintype "passive"))
    )
    (net (code "44") (name "/MIPI_TRC_DAT21") (class "Default")
      (node (ref "J32") (pin "22") (pinfunction "22_22") (pintype "passive"))
      (node (ref "RA9") (pin "14") (pinfunction "14_14") (pintype "passive"))
    )
    (net (code "45") (name "/MIPI_TRC_DAT22") (class "Default")
      (node (ref "J32") (pin "24") (pinfunction "24_24") (pintype "passive"))
      (node (ref "R463") (pin "2") (pinfunction "2_2") (pintype "passive"))
    )
    (net (code "46") (name "/MIPI_TRC_DAT23") (class "Default")
      (node (ref "J32") (pin "26") (pinfunction "26_26") (pintype "passive"))
      (node (ref "R466") (pin "2") (pinfunction "2_2") (pintype "passive"))
    )
    (net (code "47") (name "/MIPI_TRST#_R") (class "Default")
      (node (ref "J32") (pin "8") (pinfunction "8_8") (pintype "passive"))
      (node (ref "R475") (pin "2") (pinfunction "2_2") (pintype "passive"))
    )
    (net (code "48") (name "/PRG2_MDC") (class "Default")
      (node (ref "RA5") (pin "16") (pinfunction "16_16") (pintype "passive"))
    )
    (net (code "49") (name "/PRG2_MDIO") (class "Default")
      (node (ref "RA3") (pin "11") (pinfunction "11_11") (pintype "passive"))
    )
    (net (code "50") (name "/PRG2_PRU0_GP0") (class "Default")
      (node (ref "RA1") (pin "4") (pinfunction "4_4") (pintype "passive"))
      (node (ref "RA9") (pin "5") (pinfunction "5_5") (pintype "passive"))
    )
    (net (code "51") (name "/PRG2_PRU0_GP1") (class "Default")
      (node (ref "RA1") (pin "5") (pinfunction "5_5") (pintype "passive"))
      (node (ref "RA9") (pin "4") (pinfunction "4_4") (pintype "passive"))
    )
    (net (code "52") (name "/PRG2_PRU0_GP2") (class "Default")
      (node (ref "RA1") (pin "3") (pinfunction "3_3") (pintype "passive"))
      (node (ref "RA9") (pin "6") (pinfunction "6_6") (pintype "passive"))
    )
    (net (code "53") (name "/PRG2_PRU0_GP3") (class "Default")
      (node (ref "RA1") (pin "2") (pinfunction "2_2") (pintype "passive"))
      (node (ref "RA9") (pin "7") (pinfunction "7_7") (pintype "passive"))
    )
    (net (code "54") (name "/PRG2_PRU0_GP4") (class "Default")
      (node (ref "RA1") (pin "1") (pinfunction "1_1") (pintype "passive"))
      (node (ref "RA9") (pin "8") (pinfunction "8_8") (pintype "passive"))
    )
    (net (code "55") (name "/PRG2_PRU0_GP5") (class "Default")
      (node (ref "RA10") (pin "1") (pinfunction "1_1") (pintype "passive"))
      (node (ref "RA3") (pin "8") (pinfunction "8_8") (pintype "passive"))
    )
    (net (code "56") (name "/PRG2_PRU0_GP6") (class "Default")
      (node (ref "RA10") (pin "2") (pinfunction "2_2") (pintype "passive"))
      (node (ref "RA3") (pin "7") (pinfunction "7_7") (pintype "passive"))
    )
    (net (code "57") (name "/PRG2_PRU0_GP7") (class "Default")
      (node (ref "RA10") (pin "3") (pinfunction "3_3") (pintype "passive"))
      (node (ref "RA3") (pin "6") (pinfunction "6_6") (pintype "passive"))
    )
    (net (code "58") (name "/PRG2_PRU0_GP8") (class "Default")
      (node (ref "RA10") (pin "4") (pinfunction "4_4") (pintype "passive"))
      (node (ref "RA3") (pin "5") (pinfunction "5_5") (pintype "passive"))
    )
    (net (code "59") (name "/PRG2_PRU0_GP9") (class "Default")
      (node (ref "RA10") (pin "5") (pinfunction "5_5") (pintype "passive"))
      (node (ref "RA3") (pin "4") (pinfunction "4_4") (pintype "passive"))
    )
    (net (code "60") (name "/PRG2_PRU0_GP10") (class "Default")
      (node (ref "RA10") (pin "6") (pinfunction "6_6") (pintype "passive"))
      (node (ref "RA3") (pin "3") (pinfunction "3_3") (pintype "passive"))
    )
    (net (code "61") (name "/PRG2_PRU0_GP11") (class "Default")
      (node (ref "RA10") (pin "7") (pinfunction "7_7") (pintype "passive"))
      (node (ref "RA3") (pin "2") (pinfunction "2_2") (pintype "passive"))
    )
    (net (code "62") (name "/PRG2_PRU0_GP16") (class "Default")
      (node (ref "RA10") (pin "8") (pinfunction "8_8") (pintype "passive"))
      (node (ref "RA3") (pin "1") (pinfunction "1_1") (pintype "passive"))
    )
    (net (code "63") (name "/PRG2_PRU1_GP0") (class "Default")
      (node (ref "RA11") (pin "1") (pinfunction "1_1") (pintype "passive"))
      (node (ref "RA5") (pin "8") (pinfunction "8_8") (pintype "passive"))
    )
    (net (code "64") (name "/PRG2_PRU1_GP1") (class "Default")
      (node (ref "RA11") (pin "2") (pinfunction "2_2") (pintype "passive"))
      (node (ref "RA5") (pin "7") (pinfunction "7_7") (pintype "passive"))
    )
    (net (code "65") (name "/PRG2_PRU1_GP2") (class "Default")
      (node (ref "RA11") (pin "3") (pinfunction "3_3") (pintype "passive"))
      (node (ref "RA5") (pin "6") (pinfunction "6_6") (pintype "passive"))
    )
    (net (code "66") (name "/PRG2_PRU1_GP3") (class "Default")
      (node (ref "RA11") (pin "4") (pinfunction "4_4") (pintype "passive"))
      (node (ref "RA5") (pin "5") (pinfunction "5_5") (pintype "passive"))
    )
    (net (code "67") (name "/PRG2_PRU1_GP4") (class "Default")
      (node (ref "RA11") (pin "5") (pinfunction "5_5") (pintype "passive"))
      (node (ref "RA5") (pin "4") (pinfunction "4_4") (pintype "passive"))
    )
    (net (code "68") (name "/PRG2_PRU1_GP5") (class "Default")
      (node (ref "RA11") (pin "6") (pinfunction "6_6") (pintype "passive"))
      (node (ref "RA5") (pin "3") (pinfunction "3_3") (pintype "passive"))
    )
    (net (code "69") (name "/PRG2_PRU1_GP6") (class "Default")
      (node (ref "RA11") (pin "7") (pinfunction "7_7") (pintype "passive"))
      (node (ref "RA5") (pin "2") (pinfunction "2_2") (pintype "passive"))
    )
    (net (code "70") (name "/PRG2_PRU1_GP7") (class "Default")
      (node (ref "RA11") (pin "8") (pinfunction "8_8") (pintype "passive"))
      (node (ref "RA5") (pin "1") (pinfunction "1_1") (pintype "passive"))
    )
    (net (code "71") (name "/PRG2_PRU1_GP8") (class "Default")
      (node (ref "RA1") (pin "8") (pinfunction "8_8") (pintype "passive"))
      (node (ref "RA9") (pin "1") (pinfunction "1_1") (pintype "passive"))
    )
    (net (code "72") (name "/PRG2_PRU1_GP9") (class "Default")
      (node (ref "RA1") (pin "7") (pinfunction "7_7") (pintype "passive"))
      (node (ref "RA9") (pin "2") (pinfunction "2_2") (pintype "passive"))
    )
    (net (code "73") (name "/PRG2_PRU1_GP10") (class "Default")
      (node (ref "RA1") (pin "6") (pinfunction "6_6") (pintype "passive"))
      (node (ref "RA9") (pin "3") (pinfunction "3_3") (pintype "passive"))
    )
    (net (code "74") (name "/PRG2_PRU1_GP11") (class "Default")
      (node (ref "R180") (pin "1") (pinfunction "1_1") (pintype "passive"))
      (node (ref "R463") (pin "1") (pinfunction "1_1") (pintype "passive"))
    )
    (net (code "75") (name "/PRG2_PRU1_GP16") (class "Default")
      (node (ref "R183") (pin "1") (pinfunction "1_1") (pintype "passive"))
      (node (ref "R466") (pin "1") (pinfunction "1_1") (pintype "passive"))
    )
    (net (code "76") (name "/PRG2_RGMII1_RD0") (class "Default")
      (node (ref "RA1") (pin "13") (pinfunction "13_13") (pintype "passive"))
    )
    (net (code "77") (name "/PRG2_RGMII1_RD1") (class "Default")
      (node (ref "RA1") (pin "12") (pinfunction "12_12") (pintype "passive"))
    )
    (net (code "78") (name "/PRG2_RGMII1_RD2") (class "Default")
      (node (ref "RA1") (pin "14") (pinfunction "14_14") (pintype "passive"))
    )
    (net (code "79") (name "/PRG2_RGMII1_RD3") (class "Default")
      (node (ref "RA1") (pin "15") (pinfunction "15_15") (pintype "passive"))
    )
    (net (code "80") (name "/PRG2_RGMII1_RXC") (class "Default")
      (node (ref "RA3") (pin "9") (pinfunction "9_9") (pintype "passive"))
    )
    (net (code "81") (name "/PRG2_RGMII1_RX_CTL") (class "Default")
      (node (ref "RA1") (pin "16") (pinfunction "16_16") (pintype "passive"))
    )
    (net (code "82") (name "/PRG2_RGMII1_TD0") (class "Default")
      (node (ref "RA3") (pin "12") (pinfunction "12_12") (pintype "passive"))
    )
    (net (code "83") (name "/PRG2_RGMII1_TD1") (class "Default")
      (node (ref "RA3") (pin "13") (pinfunction "13_13") (pintype "passive"))
    )
    (net (code "84") (name "/PRG2_RGMII1_TD2") (class "Default")
      (node (ref "RA3") (pin "14") (pinfunction "14_14") (pintype "passive"))
    )
    (net (code "85") (name "/PRG2_RGMII1_TD3") (class "Default")
      (node (ref "RA3") (pin "15") (pinfunction "15_15") (pintype "passive"))
    )
    (net (code "86") (name "/PRG2_RGMII1_TXC") (class "Default")
      (node (ref "RA3") (pin "16") (pinfunction "16_16") (pintype "passive"))
    )
    (net (code "87") (name "/PRG2_RGMII1_TX_CTL") (class "Default")
      (node (ref "RA3") (pin "10") (pinfunction "10_10") (pintype "passive"))
    )
    (net (code "88") (name "/PRG2_RGMII2_RD0") (class "Default")
      (node (ref "RA5") (pin "9") (pinfunction "9_9") (pintype "passive"))
    )
    (net (code "89") (name "/PRG2_RGMII2_RD1") (class "Default")
      (node (ref "RA5") (pin "10") (pinfunction "10_10") (pintype "passive"))
    )
    (net (code "90") (name "/PRG2_RGMII2_RD2") (class "Default")
      (node (ref "RA5") (pin "11") (pinfunction "11_11") (pintype "passive"))
    )
    (net (code "91") (name "/PRG2_RGMII2_RD3") (class "Default")
      (node (ref "RA5") (pin "12") (pinfunction "12_12") (pintype "passive"))
    )
    (net (code "92") (name "/PRG2_RGMII2_RXC") (class "Default")
      (node (ref "RA5") (pin "14") (pinfunction "14_14") (pintype "passive"))
    )
    (net (code "93") (name "/PRG2_RGMII2_RX_CTL") (class "Default")
      (node (ref "RA5") (pin "13") (pinfunction "13_13") (pintype "passive"))
    )
    (net (code "94") (name "/PRG2_RGMII2_TD0") (class "Default")
      (node (ref "RA1") (pin "9") (pinfunction "9_9") (pintype "passive"))
    )
    (net (code "95") (name "/PRG2_RGMII2_TD1") (class "Default")
      (node (ref "RA1") (pin "10") (pinfunction "10_10") (pintype "passive"))
    )
    (net (code "96") (name "/PRG2_RGMII2_TD2") (class "Default")
      (node (ref "RA1") (pin "11") (pinfunction "11_11") (pintype "passive"))
    )
    (net (code "97") (name "/PRG2_RGMII2_TD3") (class "Default")
      (node (ref "R180") (pin "2") (pinfunction "2_2") (pintype "passive"))
    )
    (net (code "98") (name "/PRG2_RGMII2_TXC") (class "Default")
      (node (ref "R183") (pin "2") (pinfunction "2_2") (pintype "passive"))
    )
    (net (code "99") (name "/PRG2_RGMII2_TX_CTL") (class "Default")
      (node (ref "RA5") (pin "15") (pinfunction "15_15") (pintype "passive"))
    )
    (net (code "100") (name "/SEL_XDS110_INV") (class "Default")
      (node (ref "J13") (pin "8") (pinfunction "8_8") (pintype "passive"))
      (node (ref "J32") (pin "58") (pinfunction "58_58") (pintype "passive"))
      (node (ref "U39") (pin "1") (pinfunction "A_1") (pintype "input"))
      (node (ref "U41") (pin "1") (pinfunction "A_1") (pintype "input"))
      (node (ref "U42") (pin "15") (pinfunction "~{OE}_15") (pintype "input"))
      (node (ref "U90") (pin "1") (pinfunction "A_1") (pintype "input"))
      (node (ref "U92") (pin "1") (pinfunction "A_1") (pintype "input"))
    )
    (net (code "101") (name "/VCC3V3_R") (class "Default")
      (node (ref "J32") (pin "1") (pinfunction "1_1") (pintype "passive"))
      (node (ref "R184") (pin "1") (pinfunction "1_1") (pintype "passive"))
    )
    (net (code "102") (name "/cTI_TCK") (class "Default")
      (node (ref "R233") (pin "1") (pinfunction "1_1") (pintype "passive"))
      (node (ref "U42") (pin "3") (pinfunction "1B2_3") (pintype "bidirectional"))
    )
    (net (code "103") (name "DGND") (class "Default")
      (node (ref "C144") (pin "2") (pinfunction "2_2") (pintype "passive"))
      (node (ref "C166") (pin "2") (pinfunction "2_2") (pintype "passive"))
      (node (ref "C188") (pin "2") (pinfunction "2_2") (pintype "passive"))
      (node (ref "C198") (pin "2") (pinfunction "2_2") (pintype "passive"))
      (node (ref "C210") (pin "2") (pinfunction "2_2") (pintype "passive"))
      (node (ref "C214") (pin "2") (pinfunction "2_2") (pintype "passive"))
      (node (ref "C217") (pin "2") (pinfunction "2_2") (pintype "passive"))
      (node (ref "C687") (pin "1") (pinfunction "1_1") (pintype "passive"))
      (node (ref "C688") (pin "1") (pinfunction "1_1") (pintype "passive"))
      (node (ref "C689") (pin "1") (pinfunction "1_1") (pintype "passive"))
      (node (ref "C690") (pin "1") (pinfunction "1_1") (pintype "passive"))
      (node (ref "J13") (pin "10") (pinfunction "10_10") (pintype "passive"))
      (node (ref "J13") (pin "12") (pinfunction "12_12") (pintype "passive"))
      (node (ref "J13") (pin "16") (pinfunction "16_16") (pintype "passive"))
      (node (ref "J13") (pin "20") (pinfunction "20_20") (pintype "passive"))
      (node (ref "J32") (pin "16") (pinfunction "16_16") (pintype "passive"))
      (node (ref "J32") (pin "57") (pinfunction "57_57") (pintype "passive"))
      (node (ref "J32") (pin "61") (pinfunction "61_61") (pintype "passive"))
      (node (ref "J32") (pin "62") (pinfunction "62_62") (pintype "passive"))
      (node (ref "J32") (pin "63") (pinfunction "63_63") (pintype "passive"))
      (node (ref "J32") (pin "64") (pinfunction "64_64") (pintype "passive"))
      (node (ref "J43") (pin "3") (pinfunction "3_3") (pintype "passive"))
      (node (ref "R195") (pin "1") (pinfunction "1_1") (pintype "passive"))
      (node (ref "R478") (pin "1") (pinfunction "1_1") (pintype "passive"))
      (node (ref "U37") (pin "2") (pinfunction "GND_2") (pintype "power_in"))
      (node (ref "U39") (pin "3") (pinfunction "GND_3") (pintype "power_in"))
      (node (ref "U41") (pin "3") (pinfunction "GND_3") (pintype "power_in"))
      (node (ref "U42") (pin "12") (pinfunction "4A_12") (pintype "bidirectional"))
      (node (ref "U42") (pin "7") (pinfunction "2A_7") (pintype "bidirectional"))
      (node (ref "U42") (pin "8") (pinfunction "GND_8") (pintype "power_in"))
      (node (ref "U42") (pin "9") (pinfunction "3A_9") (pintype "bidirectional"))
      (node (ref "U90") (pin "3") (pinfunction "GND_3") (pintype "power_in"))
      (node (ref "U92") (pin "3") (pinfunction "GND_3") (pintype "power_in"))
    )
    (net (code "104") (name "Net-(C210-Pad1)") (class "Default")
      (node (ref "C210") (pin "1") (pinfunction "1_1") (pintype "passive"))
      (node (ref "R222") (pin "2") (pinfunction "2_2") (pintype "passive"))
    )
    (net (code "105") (name "Net-(C214-Pad1)") (class "Default")
      (node (ref "C214") (pin "1") (pinfunction "1_1") (pintype "passive"))
      (node (ref "R229") (pin "2") (pinfunction "2_2") (pintype "passive"))
    )
    (net (code "106") (name "Net-(J32-Pad6)") (class "Default")
      (node (ref "J32") (pin "6") (pinfunction "6_6") (pintype "passive"))
      (node (ref "R472") (pin "2") (pinfunction "2_2") (pintype "passive"))
    )
    (net (code "107") (name "Net-(J32-Pad12)") (class "Default")
      (node (ref "J32") (pin "12") (pinfunction "12_12") (pintype "passive"))
      (node (ref "R479") (pin "2") (pinfunction "2_2") (pintype "passive"))
    )
    (net (code "108") (name "Net-(J32-Pad15)") (class "Default")
      (node (ref "J32") (pin "15") (pinfunction "15_15") (pintype "passive"))
      (node (ref "R478") (pin "2") (pinfunction "2_2") (pintype "passive"))
    )
    (net (code "109") (name "Net-(U37-OE)") (class "Default")
      (node (ref "R218") (pin "1") (pinfunction "1_1") (pintype "passive"))
      (node (ref "U37") (pin "6") (pinfunction "OE_6") (pintype "input"))
    )
    (net (code "110") (name "Net-(U39-Y)") (class "Default")
      (node (ref "R223") (pin "2") (pinfunction "2_2") (pintype "passive"))
      (node (ref "U39") (pin "4") (pinfunction "Y_4") (pintype "output"))
    )
    (net (code "111") (name "Net-(U41-Y)") (class "Default")
      (node (ref "R233") (pin "2") (pinfunction "2_2") (pintype "passive"))
      (node (ref "U41") (pin "4") (pinfunction "Y_4") (pintype "output"))
    )
    (net (code "112") (name "Net-(U90-Y)") (class "Default")
      (node (ref "R543") (pin "2") (pinfunction "2_2") (pintype "passive"))
      (node (ref "U90") (pin "4") (pinfunction "Y_4") (pintype "output"))
    )
    (net (code "113") (name "Net-(U92-Y)") (class "Default")
      (node (ref "R565") (pin "2") (pinfunction "2_2") (pintype "passive"))
      (node (ref "U92") (pin "4") (pinfunction "Y_4") (pintype "output"))
    )
    (net (code "114") (name "VCC1V8") (class "Default")
      (node (ref "FL5") (pin "1") (pinfunction "1_1") (pintype "passive"))
    )
    (net (code "115") (name "VCC1V8_MIPI") (class "Default")
      (node (ref "C188") (pin "1") (pinfunction "1_1") (pintype "passive"))
      (node (ref "FL5") (pin "2") (pinfunction "2_2") (pintype "passive"))
      (node (ref "R214") (pin "1") (pinfunction "1_1") (pintype "passive"))
      (node (ref "R217") (pin "1") (pinfunction "1_1") (pintype "passive"))
      (node (ref "R218") (pin "2") (pinfunction "2_2") (pintype "passive"))
      (node (ref "R479") (pin "1") (pinfunction "1_1") (pintype "passive"))
      (node (ref "U37") (pin "3") (pinfunction "VCCA_3") (pintype "power_in"))
    )
    (net (code "116") (name "VCC3V3_IO") (class "Default")
      (node (ref "C144") (pin "1") (pinfunction "1_1") (pintype "passive"))
      (node (ref "C166") (pin "1") (pinfunction "1_1") (pintype "passive"))
      (node (ref "C198") (pin "1") (pinfunction "1_1") (pintype "passive"))
      (node (ref "C217") (pin "1") (pinfunction "1_1") (pintype "passive"))
      (node (ref "C687") (pin "2") (pinfunction "2_2") (pintype "passive"))
      (node (ref "C688") (pin "2") (pinfunction "2_2") (pintype "passive"))
      (node (ref "C689") (pin "2") (pinfunction "2_2") (pintype "passive"))
      (node (ref "C690") (pin "2") (pinfunction "2_2") (pintype "passive"))
      (node (ref "J13") (pin "5") (pinfunction "5_5") (pintype "passive"))
      (node (ref "J43") (pin "1") (pinfunction "1_1") (pintype "passive"))
      (node (ref "R184") (pin "2") (pinfunction "2_2") (pintype "passive"))
      (node (ref "R213") (pin "1") (pinfunction "1_1") (pintype "passive"))
      (node (ref "R221") (pin "2") (pinfunction "2_2") (pintype "passive"))
      (node (ref "R227") (pin "2") (pinfunction "2_2") (pintype "passive"))
      (node (ref "U37") (pin "7") (pinfunction "VCCB_7") (pintype "power_in"))
      (node (ref "U39") (pin "5") (pinfunction "VCC_5") (pintype "power_in"))
      (node (ref "U41") (pin "5") (pinfunction "VCC_5") (pintype "power_in"))
      (node (ref "U42") (pin "16") (pinfunction "VCC_16") (pintype "power_in"))
      (node (ref "U90") (pin "5") (pinfunction "VCC_5") (pintype "power_in"))
      (node (ref "U92") (pin "5") (pinfunction "VCC_5") (pintype "power_in"))
    )
    (net (code "117") (name "unconnected-(J13-Pad6)") (class "Default")
      (node (ref "J13") (pin "6") (pinfunction "6_6") (pintype "passive+no_connect"))
    )
    (net (code "118") (name "unconnected-(J13-Pad17)") (class "Default")
      (node (ref "J13") (pin "17") (pinfunction "17_17") (pintype "passive+no_connect"))
    )
    (net (code "119") (name "unconnected-(J13-Pad18)") (class "Default")
      (node (ref "J13") (pin "18") (pinfunction "18_18") (pintype "passive+no_connect"))
    )
    (net (code "120") (name "unconnected-(J13-Pad19)") (class "Default")
      (node (ref "J13") (pin "19") (pinfunction "19_19") (pintype "passive+no_connect"))
    )
    (net (code "121") (name "unconnected-(J32-Pad9)") (class "Default")
      (node (ref "J32") (pin "9") (pinfunction "9_9") (pintype "passive+no_connect"))
    )
    (net (code "122") (name "unconnected-(J32-Pad10)") (class "Default")
      (node (ref "J32") (pin "10") (pinfunction "10_10") (pintype "passive+no_connect"))
    )
    (net (code "123") (name "unconnected-(J32-Pad11)") (class "Default")
      (node (ref "J32") (pin "11") (pinfunction "11_11") (pintype "passive+no_connect"))
    )
    (net (code "124") (name "unconnected-(J32-Pad14)") (class "Default")
      (node (ref "J32") (pin "14") (pinfunction "14_14") (pintype "passive+no_connect"))
    )
    (net (code "125") (name "unconnected-(J32-Pad28)") (class "Default")
      (node (ref "J32") (pin "28") (pinfunction "28_28") (pintype "passive+no_connect"))
    )
    (net (code "126") (name "unconnected-(J32-Pad30)") (class "Default")
      (node (ref "J32") (pin "30") (pinfunction "30_30") (pintype "passive+no_connect"))
    )
    (net (code "127") (name "unconnected-(J32-Pad32)") (class "Default")
      (node (ref "J32") (pin "32") (pinfunction "32_32") (pintype "passive+no_connect"))
    )
    (net (code "128") (name "unconnected-(J32-Pad34)") (class "Default")
      (node (ref "J32") (pin "34") (pinfunction "34_34") (pintype "passive+no_connect"))
    )
    (net (code "129") (name "unconnected-(J32-Pad36)") (class "Default")
      (node (ref "J32") (pin "36") (pinfunction "36_36") (pintype "passive+no_connect"))
    )
    (net (code "130") (name "unconnected-(J32-Pad42)") (class "Default")
      (node (ref "J32") (pin "42") (pinfunction "42_42") (pintype "passive+no_connect"))
    )
    (net (code "131") (name "unconnected-(J32-Pad44)") (class "Default")
      (node (ref "J32") (pin "44") (pinfunction "44_44") (pintype "passive+no_connect"))
    )
    (net (code "132") (name "unconnected-(J32-Pad46)") (class "Default")
      (node (ref "J32") (pin "46") (pinfunction "46_46") (pintype "passive+no_connect"))
    )
    (net (code "133") (name "unconnected-(J32-Pad48)") (class "Default")
      (node (ref "J32") (pin "48") (pinfunction "48_48") (pintype "passive+no_connect"))
    )
    (net (code "134") (name "unconnected-(J32-Pad50)") (class "Default")
      (node (ref "J32") (pin "50") (pinfunction "50_50") (pintype "passive+no_connect"))
    )
    (net (code "135") (name "unconnected-(J32-Pad52)") (class "Default")
      (node (ref "J32") (pin "52") (pinfunction "52_52") (pintype "passive+no_connect"))
    )
    (net (code "136") (name "unconnected-(J32-Pad54)") (class "Default")
      (node (ref "J32") (pin "54") (pinfunction "54_54") (pintype "passive+no_connect"))
    )
    (net (code "137") (name "unconnected-(J32-Pad56)") (class "Default")
      (node (ref "J32") (pin "56") (pinfunction "56_56") (pintype "passive+no_connect"))
    )
    (net (code "138") (name "unconnected-(J32-Pad59)") (class "Default")
      (node (ref "J32") (pin "59") (pinfunction "59_59") (pintype "passive+no_connect"))
    )
    (net (code "139") (name "unconnected-(J32-Pad60)") (class "Default")
      (node (ref "J32") (pin "60") (pinfunction "60_60") (pintype "passive+no_connect"))
    )
    (net (code "140") (name "unconnected-(U42-2B1-Pad5)") (class "Default")
      (node (ref "U42") (pin "5") (pinfunction "2B1_5") (pintype "bidirectional+no_connect"))
    )
    (net (code "141") (name "unconnected-(U42-2B2-Pad6)") (class "Default")
      (node (ref "U42") (pin "6") (pinfunction "2B2_6") (pintype "bidirectional+no_connect"))
    )
    (net (code "142") (name "unconnected-(U42-3B1-Pad11)") (class "Default")
      (node (ref "U42") (pin "11") (pinfunction "3B1_11") (pintype "bidirectional+no_connect"))
    )
    (net (code "143") (name "unconnected-(U42-3B2-Pad10)") (class "Default")
      (node (ref "U42") (pin "10") (pinfunction "3B2_10") (pintype "bidirectional+no_connect"))
    )
    (net (code "144") (name "unconnected-(U42-4B1-Pad14)") (class "Default")
      (node (ref "U42") (pin "14") (pinfunction "4B1_14") (pintype "bidirectional+no_connect"))
    )
    (net (code "145") (name "unconnected-(U42-4B2-Pad13)") (class "Default")
      (node (ref "U42") (pin "13") (pinfunction "4B2_13") (pintype "bidirectional+no_connect"))
    )
  )
)
